# femtoduinoBLE.net
KiCad netlist of a schematic drawn in EAGLE
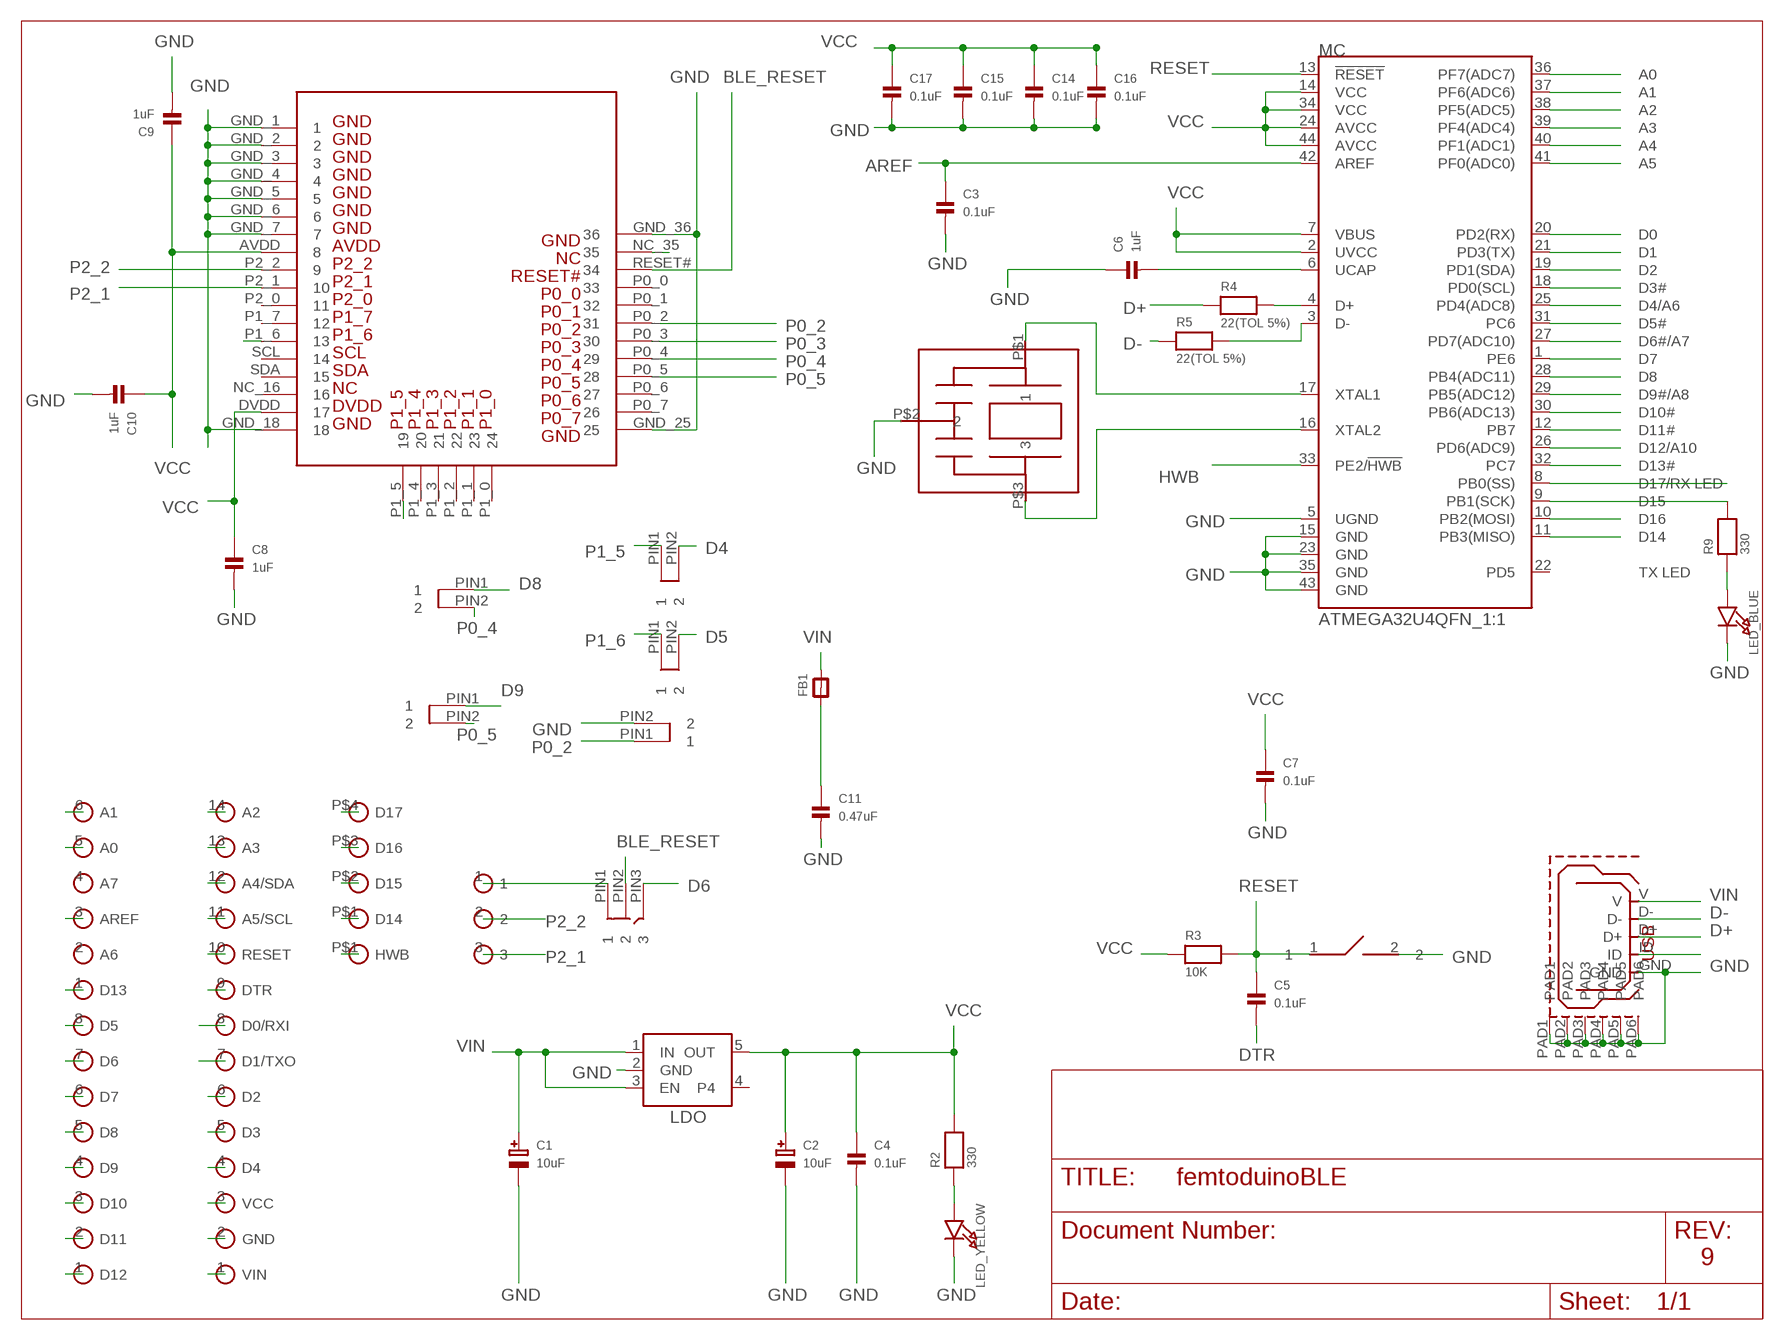
[diagram p0: schematic, sheet 1]

(export (version "E")
  (design (tool "Eeschema 10.0.6"))
  (components
    (comp (ref "BLE_CTS")
      (value "DNP")
      (footprint "eagle-import:SPST_SMD_BRIDGED")
      (libsource (lib "eagle-import") (part "SPST_SMD_BRIDGED"))
    )
    (comp (ref "C1")
      (value "10uF")
      (footprint "eagle-import:EIA3216-18_A-R")
      (libsource (lib "eagle-import") (part "CAP_TANTALUMA/3216_REFLOW"))
    )
    (comp (ref "C2")
      (value "10uF")
      (footprint "eagle-import:EIA3216-18_A-R")
      (libsource (lib "eagle-import") (part "CAP_TANTALUMA/3216_REFLOW"))
    )
    (comp (ref "C3")
      (value "0.1uF")
      (footprint "eagle-import:_0402")
      (libsource (lib "eagle-import") (part "CAP_CERAMIC_0402"))
    )
    (comp (ref "C4")
      (value "0.1uF")
      (footprint "eagle-import:_0402")
      (libsource (lib "eagle-import") (part "CAP_CERAMIC_0402"))
    )
    (comp (ref "C5")
      (value "0.1uF")
      (footprint "eagle-import:_0402")
      (libsource (lib "eagle-import") (part "CAP_CERAMIC_0402"))
    )
    (comp (ref "C6")
      (value "1uF")
      (footprint "eagle-import:_0402")
      (libsource (lib "eagle-import") (part "CAP_CERAMIC_0402"))
    )
    (comp (ref "C7")
      (value "0.1uF")
      (footprint "eagle-import:_0402")
      (libsource (lib "eagle-import") (part "CAP_CERAMIC_0402"))
    )
    (comp (ref "C8")
      (value "1uF")
      (footprint "eagle-import:0402")
      (libsource (lib "eagle-import") (part "CAP_CERAMIC0402"))
    )
    (comp (ref "C9")
      (value "1uF")
      (footprint "eagle-import:0402")
      (libsource (lib "eagle-import") (part "CAP_CERAMIC0402"))
    )
    (comp (ref "C10")
      (value "1uF")
      (footprint "eagle-import:0402")
      (libsource (lib "eagle-import") (part "CAP_CERAMIC0402"))
    )
    (comp (ref "C11")
      (value "0.47uF")
      (footprint "eagle-import:_0402")
      (libsource (lib "eagle-import") (part "CAP_CERAMIC_0402"))
    )
    (comp (ref "C14")
      (value "0.1uF")
      (footprint "eagle-import:_0402")
      (libsource (lib "eagle-import") (part "CAP_CERAMIC_0402"))
    )
    (comp (ref "C15")
      (value "0.1uF")
      (footprint "eagle-import:_0402")
      (libsource (lib "eagle-import") (part "CAP_CERAMIC_0402"))
    )
    (comp (ref "C16")
      (value "0.1uF")
      (footprint "eagle-import:_0402")
      (libsource (lib "eagle-import") (part "CAP_CERAMIC_0402"))
    )
    (comp (ref "C17")
      (value "0.1uF")
      (footprint "eagle-import:_0402")
      (libsource (lib "eagle-import") (part "CAP_CERAMIC_0402"))
    )
    (comp (ref "FB1")
      (value "FERRITE")
      (footprint "eagle-import:0603")
      (libsource (lib "eagle-import") (part "FERRITE"))
    )
    (comp (ref "LED_BLUE")
      (value "LED0603_NOOUTLINE")
      (footprint "eagle-import:CHIPLED_0603_NOOUTLINE")
      (libsource (lib "eagle-import") (part "LED0603_NOOUTLINE"))
    )
    (comp (ref "LED_YELLOW")
      (value "LED0603_NOOUTLINE")
      (footprint "eagle-import:CHIPLED_0603_NOOUTLINE")
      (libsource (lib "eagle-import") (part "LED0603_NOOUTLINE"))
    )
    (comp (ref "MC")
      (value "ATMEGA32U4QFN_1:1")
      (footprint "eagle-import:QFN-44-NOPAD_1_1")
      (libsource (lib "eagle-import") (part "ATMEGA32U4QFN_1{colon}1"))
    )
    (comp (ref "R2")
      (value "330")
      (footprint "eagle-import:_0402")
      (libsource (lib "eagle-import") (part "RESISTOR_0402"))
    )
    (comp (ref "R3")
      (value "10K")
      (footprint "eagle-import:_0402")
      (libsource (lib "eagle-import") (part "RESISTOR_0402"))
    )
    (comp (ref "R4")
      (value "22(TOL 5%)")
      (footprint "eagle-import:0402")
      (libsource (lib "eagle-import") (part "RESISTOR0402"))
    )
    (comp (ref "R5")
      (value "22(TOL 5%)")
      (footprint "eagle-import:0402")
      (libsource (lib "eagle-import") (part "RESISTOR0402"))
    )
    (comp (ref "R9")
      (value "330")
      (footprint "eagle-import:_0402")
      (libsource (lib "eagle-import") (part "RESISTOR_0402"))
    )
    (comp (ref "U$1")
      (value "USB_MICROB")
      (footprint "eagle-import:USB_MICROB_PACKAGE")
      (libsource (lib "eagle-import") (part "USB_MICROB"))
    )
    (comp (ref "U$2")
      (value "CSTCE16MOV51-RO")
      (footprint "eagle-import:CSTCE16M0V51-RO_PACKAGE")
      (libsource (lib "eagle-import") (part "CSTCE16MOV51-RO"))
    )
    (comp (ref "U$4")
      (value "LDO_REGULATOR")
      (footprint "eagle-import:LDO_REGULATOR")
      (libsource (lib "eagle-import") (part "LDO_REGULATOR"))
    )
    (comp (ref "U$5")
      (value "05_PINHEAD_1X6")
      (footprint "eagle-import:05_PINHEAD_1X6_PACKAGE")
      (libsource (lib "eagle-import") (part "05_PINHEAD_1X6"))
    )
    (comp (ref "U$6")
      (value "05_PINHEAD_1X8")
      (footprint "eagle-import:05_PINHEAD_1X8_PACKAGE")
      (libsource (lib "eagle-import") (part "05_PINHEAD_1X8"))
    )
    (comp (ref "U$7")
      (value "05_PINHEAD_1X14")
      (footprint "eagle-import:05_PINHEAD_1X14_PACKAGE")
      (libsource (lib "eagle-import") (part "05_PINHEAD_1X14"))
    )
    (comp (ref "U$9")
      (value "DNP")
      (footprint "eagle-import:SPST_SMD")
      (libsource (lib "eagle-import") (part "SPST_SMD"))
    )
    (comp (ref "U$10")
      (value "05_PINHEAD_1X4")
      (footprint "eagle-import:05_PINHEAD_1X4_PACKAGE")
      (libsource (lib "eagle-import") (part "05_PINHEAD_1X4"))
    )
    (comp (ref "U$11")
      (value "05_PINHEAD_1X1")
      (footprint "eagle-import:05_PINHEAD_1X1_PACKAGE")
      (libsource (lib "eagle-import") (part "05_PINHEAD_1X1"))
    )
    (comp (ref "U$12")
      (value "BLE113-A")
      (footprint "eagle-import:BLE113-A")
      (libsource (lib "eagle-import") (part "BLE113-A"))
    )
    (comp (ref "U$13")
      (value "DNP")
      (footprint "eagle-import:SPST_SMD_BRIDGED")
      (libsource (lib "eagle-import") (part "SPST_SMD_BRIDGED"))
    )
    (comp (ref "U$14")
      (value "DNP")
      (footprint "eagle-import:SPST_SMD_BRIDGED")
      (libsource (lib "eagle-import") (part "SPST_SMD_BRIDGED"))
    )
    (comp (ref "U$15")
      (value "DNP")
      (footprint "eagle-import:SPST_SMD_BRIDGED")
      (libsource (lib "eagle-import") (part "SPST_SMD_BRIDGED"))
    )
    (comp (ref "U$16")
      (value "DNP")
      (footprint "eagle-import:SPST_SMD_BRIDGED")
      (libsource (lib "eagle-import") (part "SPST_SMD_BRIDGED"))
    )
    (comp (ref "U$19")
      (value "DNP")
      (footprint "eagle-import:SPST_3_SMD")
      (libsource (lib "eagle-import") (part "SPST_3_SMD"))
    )
    (comp (ref "U$20")
      (value "05_PINHEAD_HEADER_1X3")
      (footprint "eagle-import:05_PINHEAD_1X3_HEAD_PACKAGE")
      (libsource (lib "eagle-import") (part "05_PINHEAD_HEADER_1X3"))
    )
  )
  (nets
    (net (code "1") (name "/A0") (class "Default")
      (node (ref "MC") (pin "36") (pinfunction "PF7(ADC7)_36") (pintype "bidirectional"))
      (node (ref "U$5") (pin "5") (pinfunction "A0_5") (pintype "bidirectional"))
    )
    (net (code "2") (name "/A1") (class "Default")
      (node (ref "MC") (pin "37") (pinfunction "PF6(ADC6)_37") (pintype "bidirectional"))
      (node (ref "U$5") (pin "6") (pinfunction "A1_6") (pintype "bidirectional"))
    )
    (net (code "3") (name "/A2") (class "Default")
      (node (ref "MC") (pin "38") (pinfunction "PF5(ADC5)_38") (pintype "bidirectional"))
      (node (ref "U$7") (pin "14") (pinfunction "A2_14") (pintype "bidirectional"))
    )
    (net (code "4") (name "/A3") (class "Default")
      (node (ref "MC") (pin "39") (pinfunction "PF4(ADC4)_39") (pintype "bidirectional"))
      (node (ref "U$7") (pin "13") (pinfunction "A3_13") (pintype "bidirectional"))
    )
    (net (code "5") (name "/A4") (class "Default")
      (node (ref "MC") (pin "40") (pinfunction "PF1(ADC1)_40") (pintype "bidirectional"))
      (node (ref "U$7") (pin "12") (pinfunction "A4/SDA_12") (pintype "bidirectional"))
    )
    (net (code "6") (name "/A5") (class "Default")
      (node (ref "MC") (pin "41") (pinfunction "PF0(ADC0)_41") (pintype "bidirectional"))
      (node (ref "U$7") (pin "11") (pinfunction "A5/SCL_11") (pintype "bidirectional"))
    )
    (net (code "7") (name "/AREF") (class "Default")
      (node (ref "C3") (pin "1") (pinfunction "P$1_1") (pintype "passive"))
      (node (ref "MC") (pin "42") (pinfunction "AREF_42") (pintype "bidirectional"))
      (node (ref "U$5") (pin "3") (pinfunction "AREF_3") (pintype "bidirectional"))
    )
    (net (code "8") (name "/BLE_RESET") (class "Default")
      (node (ref "U$12") (pin "RESET#") (pinfunction "34_RESET#") (pintype "bidirectional"))
      (node (ref "U$19") (pin "PIN2") (pinfunction "2_PIN2") (pintype "bidirectional"))
    )
    (net (code "9") (name "/D+") (class "Default")
      (node (ref "R4") (pin "1") (pinfunction "1_1") (pintype "passive"))
      (node (ref "U$1") (pin "D+") (pinfunction "D+_D+") (pintype "bidirectional"))
    )
    (net (code "10") (name "/D-") (class "Default")
      (node (ref "R5") (pin "1") (pinfunction "1_1") (pintype "passive"))
      (node (ref "U$1") (pin "D-") (pinfunction "D-_D-") (pintype "bidirectional"))
    )
    (net (code "11") (name "/D2") (class "Default")
      (node (ref "MC") (pin "19") (pinfunction "PD1(SDA)_19") (pintype "bidirectional"))
      (node (ref "U$7") (pin "6") (pinfunction "D2_6") (pintype "bidirectional"))
    )
    (net (code "12") (name "/D3") (class "Default")
      (node (ref "MC") (pin "18") (pinfunction "PD0(SCL)_18") (pintype "bidirectional"))
      (node (ref "U$7") (pin "5") (pinfunction "D3_5") (pintype "bidirectional"))
    )
    (net (code "13") (name "/D4") (class "Default")
      (node (ref "MC") (pin "25") (pinfunction "PD4(ADC8)_25") (pintype "bidirectional"))
      (node (ref "U$16") (pin "PIN2") (pinfunction "2_PIN2") (pintype "bidirectional"))
      (node (ref "U$7") (pin "4") (pinfunction "D4_4") (pintype "bidirectional"))
    )
    (net (code "14") (name "/D5") (class "Default")
      (node (ref "MC") (pin "31") (pinfunction "PC6_31") (pintype "bidirectional"))
      (node (ref "U$15") (pin "PIN2") (pinfunction "2_PIN2") (pintype "bidirectional"))
      (node (ref "U$6") (pin "8") (pinfunction "D5_8") (pintype "bidirectional"))
    )
    (net (code "15") (name "/D6") (class "Default")
      (node (ref "MC") (pin "27") (pinfunction "PD7(ADC10)_27") (pintype "bidirectional"))
      (node (ref "U$19") (pin "PIN3") (pinfunction "3_PIN3") (pintype "bidirectional"))
      (node (ref "U$6") (pin "7") (pinfunction "D6_7") (pintype "bidirectional"))
    )
    (net (code "16") (name "/D7") (class "Default")
      (node (ref "MC") (pin "1") (pinfunction "PE6_1") (pintype "bidirectional"))
      (node (ref "U$6") (pin "6") (pinfunction "D7_6") (pintype "bidirectional"))
    )
    (net (code "17") (name "/D8") (class "Default")
      (node (ref "MC") (pin "28") (pinfunction "PB4(ADC11)_28") (pintype "bidirectional"))
      (node (ref "U$13") (pin "PIN1") (pinfunction "1_PIN1") (pintype "bidirectional"))
      (node (ref "U$6") (pin "5") (pinfunction "D8_5") (pintype "bidirectional"))
    )
    (net (code "18") (name "/D9") (class "Default")
      (node (ref "MC") (pin "29") (pinfunction "PB5(ADC12)_29") (pintype "bidirectional"))
      (node (ref "U$14") (pin "PIN1") (pinfunction "1_PIN1") (pintype "bidirectional"))
      (node (ref "U$6") (pin "4") (pinfunction "D9_4") (pintype "bidirectional"))
    )
    (net (code "19") (name "/D10") (class "Default")
      (node (ref "MC") (pin "30") (pinfunction "PB6(ADC13)_30") (pintype "bidirectional"))
      (node (ref "U$6") (pin "3") (pinfunction "D10_3") (pintype "bidirectional"))
    )
    (net (code "20") (name "/D11") (class "Default")
      (node (ref "MC") (pin "12") (pinfunction "PB7_12") (pintype "bidirectional"))
      (node (ref "U$6") (pin "2") (pinfunction "D11_2") (pintype "bidirectional"))
    )
    (net (code "21") (name "/D12") (class "Default")
      (node (ref "MC") (pin "26") (pinfunction "PD6(ADC9)_26") (pintype "bidirectional"))
      (node (ref "U$6") (pin "1") (pinfunction "D12_1") (pintype "bidirectional"))
    )
    (net (code "22") (name "/D13") (class "Default")
      (node (ref "MC") (pin "32") (pinfunction "PC7_32") (pintype "bidirectional"))
      (node (ref "U$5") (pin "1") (pinfunction "D13_1") (pintype "bidirectional"))
    )
    (net (code "23") (name "/D14") (class "Default")
      (node (ref "MC") (pin "11") (pinfunction "PB3(MISO)_11") (pintype "bidirectional"))
      (node (ref "U$10") (pin "P$1") (pinfunction "D14_P$1") (pintype "bidirectional"))
    )
    (net (code "24") (name "/D15") (class "Default")
      (node (ref "MC") (pin "9") (pinfunction "PB1(SCK)_9") (pintype "bidirectional"))
      (node (ref "R9") (pin "2") (pinfunction "2_2") (pintype "passive"))
      (node (ref "U$10") (pin "P$2") (pinfunction "D15_P$2") (pintype "bidirectional"))
    )
    (net (code "25") (name "/D16") (class "Default")
      (node (ref "MC") (pin "10") (pinfunction "PB2(MOSI)_10") (pintype "bidirectional"))
      (node (ref "U$10") (pin "P$3") (pinfunction "D16_P$3") (pintype "bidirectional"))
    )
    (net (code "26") (name "/D17") (class "Default")
      (node (ref "MC") (pin "8") (pinfunction "PB0(SS)_8") (pintype "bidirectional"))
      (node (ref "U$10") (pin "P$4") (pinfunction "D17_P$4") (pintype "bidirectional"))
    )
    (net (code "27") (name "/DTR") (class "Default")
      (node (ref "C5") (pin "2") (pinfunction "P$2_2") (pintype "passive"))
      (node (ref "U$7") (pin "9") (pinfunction "DTR_9") (pintype "bidirectional"))
    )
    (net (code "28") (name "/GND") (class "Default")
      (node (ref "BLE_CTS") (pin "PIN2") (pinfunction "2_PIN2") (pintype "bidirectional"))
      (node (ref "C1") (pin "-") (pinfunction "-_-") (pintype "passive"))
      (node (ref "C10") (pin "2") (pinfunction "P$2_2") (pintype "passive"))
      (node (ref "C11") (pin "2") (pinfunction "P$2_2") (pintype "passive"))
      (node (ref "C14") (pin "2") (pinfunction "P$2_2") (pintype "passive"))
      (node (ref "C15") (pin "2") (pinfunction "P$2_2") (pintype "passive"))
      (node (ref "C16") (pin "2") (pinfunction "P$2_2") (pintype "passive"))
      (node (ref "C17") (pin "2") (pinfunction "P$2_2") (pintype "passive"))
      (node (ref "C2") (pin "-") (pinfunction "-_-") (pintype "passive"))
      (node (ref "C3") (pin "2") (pinfunction "P$2_2") (pintype "passive"))
      (node (ref "C4") (pin "2") (pinfunction "P$2_2") (pintype "passive"))
      (node (ref "C6") (pin "1") (pinfunction "P$1_1") (pintype "passive"))
      (node (ref "C7") (pin "2") (pinfunction "P$2_2") (pintype "passive"))
      (node (ref "C8") (pin "2") (pinfunction "P$2_2") (pintype "passive"))
      (node (ref "C9") (pin "2") (pinfunction "P$2_2") (pintype "passive"))
      (node (ref "LED_BLUE") (pin "C") (pinfunction "C_C") (pintype "passive"))
      (node (ref "LED_YELLOW") (pin "C") (pinfunction "C_C") (pintype "passive"))
      (node (ref "MC") (pin "15") (pinfunction "GND_15") (pintype "bidirectional"))
      (node (ref "MC") (pin "23") (pinfunction "GND_23") (pintype "bidirectional"))
      (node (ref "MC") (pin "35") (pinfunction "GND_35") (pintype "bidirectional"))
      (node (ref "MC") (pin "43") (pinfunction "GND_43") (pintype "bidirectional"))
      (node (ref "MC") (pin "5") (pinfunction "UGND_5") (pintype "bidirectional"))
      (node (ref "U$1") (pin "GND") (pinfunction "GND_GND") (pintype "bidirectional"))
      (node (ref "U$1") (pin "PAD1") (pinfunction "PAD1_PAD1") (pintype "bidirectional"))
      (node (ref "U$1") (pin "PAD2") (pinfunction "PAD2_PAD2") (pintype "bidirectional"))
      (node (ref "U$1") (pin "PAD3") (pinfunction "PAD3_PAD3") (pintype "bidirectional"))
      (node (ref "U$1") (pin "PAD4") (pinfunction "PAD4_PAD4") (pintype "bidirectional"))
      (node (ref "U$1") (pin "PAD5") (pinfunction "PAD5_PAD5") (pintype "bidirectional"))
      (node (ref "U$1") (pin "PAD6") (pinfunction "PAD6_PAD6") (pintype "bidirectional"))
      (node (ref "U$12") (pin "GND_1") (pinfunction "1_GND_1") (pintype "bidirectional"))
      (node (ref "U$12") (pin "GND_18") (pinfunction "18_GND_18") (pintype "bidirectional"))
      (node (ref "U$12") (pin "GND_2") (pinfunction "2_GND_2") (pintype "bidirectional"))
      (node (ref "U$12") (pin "GND_25") (pinfunction "25_GND_25") (pintype "bidirectional"))
      (node (ref "U$12") (pin "GND_3") (pinfunction "3_GND_3") (pintype "bidirectional"))
      (node (ref "U$12") (pin "GND_36") (pinfunction "36_GND_36") (pintype "bidirectional"))
      (node (ref "U$12") (pin "GND_4") (pinfunction "4_GND_4") (pintype "bidirectional"))
      (node (ref "U$12") (pin "GND_5") (pinfunction "5_GND_5") (pintype "bidirectional"))
      (node (ref "U$12") (pin "GND_6") (pinfunction "6_GND_6") (pintype "bidirectional"))
      (node (ref "U$12") (pin "GND_7") (pinfunction "7_GND_7") (pintype "bidirectional"))
      (node (ref "U$2") (pin "P$2") (pinfunction "2_P$2") (pintype "bidirectional"))
      (node (ref "U$4") (pin "2") (pinfunction "GND_2") (pintype "bidirectional"))
      (node (ref "U$7") (pin "2") (pinfunction "GND_2") (pintype "bidirectional"))
      (node (ref "U$9") (pin "2") (pinfunction "2_2") (pintype "bidirectional"))
    )
    (net (code "29") (name "/HWB") (class "Default")
      (node (ref "MC") (pin "33") (pinfunction "PE2/~{HWB}_33") (pintype "bidirectional"))
      (node (ref "U$11") (pin "P$1") (pinfunction "HWB_P$1") (pintype "bidirectional"))
    )
    (net (code "30") (name "/P0_2") (class "Default")
      (node (ref "BLE_CTS") (pin "PIN1") (pinfunction "1_PIN1") (pintype "bidirectional"))
      (node (ref "U$12") (pin "P0_2") (pinfunction "31_P0_2") (pintype "bidirectional"))
    )
    (net (code "31") (name "/P0_3") (class "Default")
      (node (ref "U$12") (pin "P0_3") (pinfunction "30_P0_3") (pintype "bidirectional"))
    )
    (net (code "32") (name "/P0_4") (class "Default")
      (node (ref "U$12") (pin "P0_4") (pinfunction "29_P0_4") (pintype "bidirectional"))
      (node (ref "U$13") (pin "PIN2") (pinfunction "2_PIN2") (pintype "bidirectional"))
    )
    (net (code "33") (name "/P0_5") (class "Default")
      (node (ref "U$12") (pin "P0_5") (pinfunction "28_P0_5") (pintype "bidirectional"))
      (node (ref "U$14") (pin "PIN2") (pinfunction "2_PIN2") (pintype "bidirectional"))
    )
    (net (code "34") (name "/P1_5") (class "Default")
      (node (ref "U$12") (pin "P1_5") (pinfunction "19_P1_5") (pintype "bidirectional"))
      (node (ref "U$16") (pin "PIN1") (pinfunction "1_PIN1") (pintype "bidirectional"))
    )
    (net (code "35") (name "/P1_6") (class "Default")
      (node (ref "U$12") (pin "P1_6") (pinfunction "13_P1_6") (pintype "bidirectional"))
      (node (ref "U$15") (pin "PIN1") (pinfunction "1_PIN1") (pintype "bidirectional"))
    )
    (net (code "36") (name "/P2_1") (class "Default")
      (node (ref "U$12") (pin "P2_1") (pinfunction "10_P2_1") (pintype "bidirectional"))
      (node (ref "U$20") (pin "3") (pinfunction "3_3") (pintype "bidirectional"))
    )
    (net (code "37") (name "/P2_2") (class "Default")
      (node (ref "U$12") (pin "P2_2") (pinfunction "9_P2_2") (pintype "bidirectional"))
      (node (ref "U$20") (pin "2") (pinfunction "2_2") (pintype "bidirectional"))
    )
    (net (code "38") (name "/RESET") (class "Default")
      (node (ref "C5") (pin "1") (pinfunction "P$1_1") (pintype "passive"))
      (node (ref "MC") (pin "13") (pinfunction "~{RESET}_13") (pintype "bidirectional"))
      (node (ref "R3") (pin "2") (pinfunction "2_2") (pintype "passive"))
      (node (ref "U$7") (pin "10") (pinfunction "RESET_10") (pintype "bidirectional"))
      (node (ref "U$9") (pin "1") (pinfunction "1_1") (pintype "bidirectional"))
    )
    (net (code "39") (name "/RXI") (class "Default")
      (node (ref "MC") (pin "20") (pinfunction "PD2(RX)_20") (pintype "bidirectional"))
      (node (ref "U$7") (pin "8") (pinfunction "D0/RXI_8") (pintype "bidirectional"))
    )
    (net (code "40") (name "/TXO") (class "Default")
      (node (ref "MC") (pin "21") (pinfunction "PD3(TX)_21") (pintype "bidirectional"))
      (node (ref "U$7") (pin "7") (pinfunction "D1/TXO_7") (pintype "bidirectional"))
    )
    (net (code "41") (name "/VCC") (class "Default")
      (node (ref "C10") (pin "1") (pinfunction "P$1_1") (pintype "passive"))
      (node (ref "C14") (pin "1") (pinfunction "P$1_1") (pintype "passive"))
      (node (ref "C15") (pin "1") (pinfunction "P$1_1") (pintype "passive"))
      (node (ref "C16") (pin "1") (pinfunction "P$1_1") (pintype "passive"))
      (node (ref "C17") (pin "1") (pinfunction "P$1_1") (pintype "passive"))
      (node (ref "C2") (pin "+") (pinfunction "+_+") (pintype "passive"))
      (node (ref "C4") (pin "1") (pinfunction "P$1_1") (pintype "passive"))
      (node (ref "C7") (pin "1") (pinfunction "P$1_1") (pintype "passive"))
      (node (ref "C8") (pin "1") (pinfunction "P$1_1") (pintype "passive"))
      (node (ref "C9") (pin "1") (pinfunction "P$1_1") (pintype "passive"))
      (node (ref "MC") (pin "14") (pinfunction "VCC_14") (pintype "bidirectional"))
      (node (ref "MC") (pin "2") (pinfunction "UVCC_2") (pintype "bidirectional"))
      (node (ref "MC") (pin "24") (pinfunction "AVCC_24") (pintype "bidirectional"))
      (node (ref "MC") (pin "34") (pinfunction "VCC_34") (pintype "bidirectional"))
      (node (ref "MC") (pin "44") (pinfunction "AVCC_44") (pintype "bidirectional"))
      (node (ref "MC") (pin "7") (pinfunction "VBUS_7") (pintype "bidirectional"))
      (node (ref "R2") (pin "2") (pinfunction "2_2") (pintype "passive"))
      (node (ref "R3") (pin "1") (pinfunction "1_1") (pintype "passive"))
      (node (ref "U$12") (pin "AVDD") (pinfunction "8_AVDD") (pintype "bidirectional"))
      (node (ref "U$12") (pin "DVDD") (pinfunction "17_DVDD") (pintype "bidirectional"))
      (node (ref "U$4") (pin "5") (pinfunction "OUT_5") (pintype "bidirectional"))
      (node (ref "U$7") (pin "3") (pinfunction "VCC_3") (pintype "bidirectional"))
    )
    (net (code "42") (name "/VIN") (class "Default")
      (node (ref "C1") (pin "+") (pinfunction "+_+") (pintype "passive"))
      (node (ref "FB1") (pin "2") (pinfunction "P$2_2") (pintype "passive"))
      (node (ref "U$1") (pin "V") (pinfunction "V_V") (pintype "bidirectional"))
      (node (ref "U$4") (pin "1") (pinfunction "IN_1") (pintype "bidirectional"))
      (node (ref "U$4") (pin "3") (pinfunction "EN_3") (pintype "bidirectional"))
      (node (ref "U$7") (pin "1") (pinfunction "VIN_1") (pintype "bidirectional"))
    )
    (net (code "43") (name "Net-(C6-P$2)") (class "Default")
      (node (ref "C6") (pin "2") (pinfunction "P$2_2") (pintype "passive"))
      (node (ref "MC") (pin "6") (pinfunction "UCAP_6") (pintype "bidirectional"))
    )
    (net (code "44") (name "Net-(C11-P$1)") (class "Default")
      (node (ref "C11") (pin "1") (pinfunction "P$1_1") (pintype "passive"))
      (node (ref "FB1") (pin "1") (pinfunction "P$1_1") (pintype "passive"))
    )
    (net (code "45") (name "Net-(LED_BLUE-PadA)") (class "Default")
      (node (ref "LED_BLUE") (pin "A") (pinfunction "A_A") (pintype "passive"))
      (node (ref "R9") (pin "1") (pinfunction "1_1") (pintype "passive"))
    )
    (net (code "46") (name "Net-(LED_YELLOW-PadA)") (class "Default")
      (node (ref "LED_YELLOW") (pin "A") (pinfunction "A_A") (pintype "passive"))
      (node (ref "R2") (pin "1") (pinfunction "1_1") (pintype "passive"))
    )
    (net (code "47") (name "Net-(MC-D+)") (class "Default")
      (node (ref "MC") (pin "4") (pinfunction "D+_4") (pintype "bidirectional"))
      (node (ref "R4") (pin "2") (pinfunction "2_2") (pintype "passive"))
    )
    (net (code "48") (name "Net-(MC-D-)") (class "Default")
      (node (ref "MC") (pin "3") (pinfunction "D-_3") (pintype "bidirectional"))
      (node (ref "R5") (pin "2") (pinfunction "2_2") (pintype "passive"))
    )
    (net (code "49") (name "Net-(MC-XTAL1)") (class "Default")
      (node (ref "MC") (pin "17") (pinfunction "XTAL1_17") (pintype "bidirectional"))
      (node (ref "U$2") (pin "P$1") (pinfunction "1_P$1") (pintype "bidirectional"))
    )
    (net (code "50") (name "Net-(MC-XTAL2)") (class "Default")
      (node (ref "MC") (pin "16") (pinfunction "XTAL2_16") (pintype "bidirectional"))
      (node (ref "U$2") (pin "P$3") (pinfunction "3_P$3") (pintype "bidirectional"))
    )
    (net (code "51") (name "Net-(U$19-1)") (class "Default")
      (node (ref "U$19") (pin "PIN1") (pinfunction "1_PIN1") (pintype "bidirectional"))
      (node (ref "U$20") (pin "1") (pinfunction "1_1") (pintype "bidirectional"))
    )
    (net (code "52") (name "unconnected-(MC-PD5-Pad22)") (class "Default")
      (node (ref "MC") (pin "22") (pinfunction "PD5_22") (pintype "bidirectional"))
    )
    (net (code "53") (name "unconnected-(U$1-PadID)") (class "Default")
      (node (ref "U$1") (pin "ID") (pinfunction "ID_ID") (pintype "bidirectional"))
    )
    (net (code "54") (name "unconnected-(U$4-P4-Pad4)") (class "Default")
      (node (ref "U$4") (pin "4") (pinfunction "P4_4") (pintype "bidirectional"))
    )
    (net (code "55") (name "unconnected-(U$5-A6-Pad2)") (class "Default")
      (node (ref "U$5") (pin "2") (pinfunction "A6_2") (pintype "bidirectional"))
    )
    (net (code "56") (name "unconnected-(U$5-A7-Pad4)") (class "Default")
      (node (ref "U$5") (pin "4") (pinfunction "A7_4") (pintype "bidirectional"))
    )
    (net (code "57") (name "unconnected-(U$12-11-PadP2_0)") (class "Default")
      (node (ref "U$12") (pin "P2_0") (pinfunction "11_P2_0") (pintype "bidirectional"))
    )
    (net (code "58") (name "unconnected-(U$12-12-PadP1_7)") (class "Default")
      (node (ref "U$12") (pin "P1_7") (pinfunction "12_P1_7") (pintype "bidirectional"))
    )
    (net (code "59") (name "unconnected-(U$12-14-PadSCL)") (class "Default")
      (node (ref "U$12") (pin "SCL") (pinfunction "14_SCL") (pintype "bidirectional"))
    )
    (net (code "60") (name "unconnected-(U$12-15-PadSDA)") (class "Default")
      (node (ref "U$12") (pin "SDA") (pinfunction "15_SDA") (pintype "bidirectional"))
    )
    (net (code "61") (name "unconnected-(U$12-16-PadNC_16)") (class "Default")
      (node (ref "U$12") (pin "NC_16") (pinfunction "16_NC_16") (pintype "bidirectional"))
    )
    (net (code "62") (name "unconnected-(U$12-20-PadP1_4)") (class "Default")
      (node (ref "U$12") (pin "P1_4") (pinfunction "20_P1_4") (pintype "bidirectional"))
    )
    (net (code "63") (name "unconnected-(U$12-21-PadP1_3)") (class "Default")
      (node (ref "U$12") (pin "P1_3") (pinfunction "21_P1_3") (pintype "bidirectional"))
    )
    (net (code "64") (name "unconnected-(U$12-22-PadP1_2)") (class "Default")
      (node (ref "U$12") (pin "P1_2") (pinfunction "22_P1_2") (pintype "bidirectional"))
    )
    (net (code "65") (name "unconnected-(U$12-23-PadP1_1)") (class "Default")
      (node (ref "U$12") (pin "P1_1") (pinfunction "23_P1_1") (pintype "bidirectional"))
    )
    (net (code "66") (name "unconnected-(U$12-24-PadP1_0)") (class "Default")
      (node (ref "U$12") (pin "P1_0") (pinfunction "24_P1_0") (pintype "bidirectional"))
    )
    (net (code "67") (name "unconnected-(U$12-26-PadP0_7)") (class "Default")
      (node (ref "U$12") (pin "P0_7") (pinfunction "26_P0_7") (pintype "bidirectional"))
    )
    (net (code "68") (name "unconnected-(U$12-27-PadP0_6)") (class "Default")
      (node (ref "U$12") (pin "P0_6") (pinfunction "27_P0_6") (pintype "bidirectional"))
    )
    (net (code "69") (name "unconnected-(U$12-32-PadP0_1)") (class "Default")
      (node (ref "U$12") (pin "P0_1") (pinfunction "32_P0_1") (pintype "bidirectional"))
    )
    (net (code "70") (name "unconnected-(U$12-33-PadP0_0)") (class "Default")
      (node (ref "U$12") (pin "P0_0") (pinfunction "33_P0_0") (pintype "bidirectional"))
    )
    (net (code "71") (name "unconnected-(U$12-35-PadNC_35)") (class "Default")
      (node (ref "U$12") (pin "NC_35") (pinfunction "35_NC_35") (pintype "bidirectional"))
    )
  )
)
